# Power_supply.net
KiCad netlist of a schematic drawn in Altium Designer
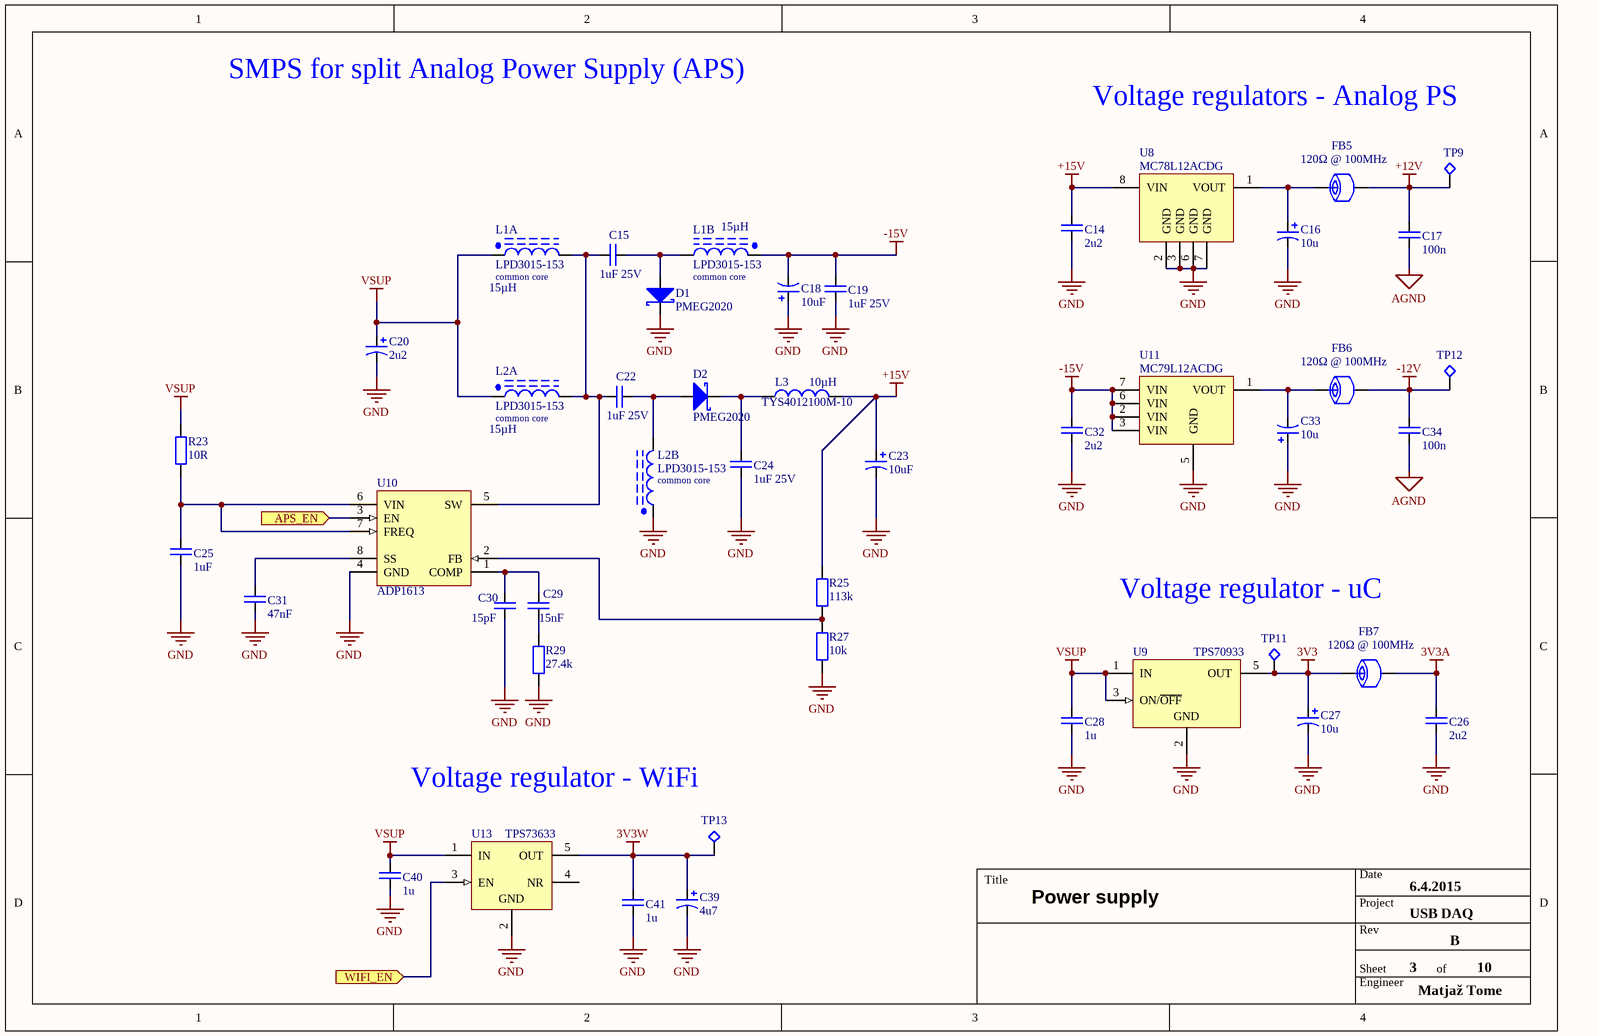
[diagram p0: Power_supply.SchDoc]

(export (version "E")
  (design (tool "Eeschema 10.0.6"))
  (components
    (comp (ref "C14")
      (value "2u2")
      (footprint "C_0603")
      (description "Generic capacitor")
      (libsource (lib "DAQ_REV_B") (part "Capacitor"))
    )
    (comp (ref "C15")
      (value "1uF 25V")
      (footprint "C_0603")
      (description "Generic capacitor")
      (libsource (lib "DAQ_REV_B") (part "Capacitor"))
    )
    (comp (ref "C16")
      (value "10u")
      (footprint "Tantalum Case A")
      (description "Generic polarized capacitor")
      (libsource (lib "DAQ_REV_B") (part "Capacitor - polarized"))
    )
    (comp (ref "C17")
      (value "100n")
      (footprint "C_0603")
      (description "Generic capacitor")
      (libsource (lib "DAQ_REV_B") (part "Capacitor"))
    )
    (comp (ref "C18")
      (value "10uF")
      (footprint "Tantalum Case A")
      (description "Generic polarized capacitor")
      (libsource (lib "DAQ_REV_B") (part "Capacitor - polarized"))
    )
    (comp (ref "C19")
      (value "1uF 25V")
      (footprint "C_0603")
      (description "Generic capacitor")
      (libsource (lib "DAQ_REV_B") (part "Capacitor"))
    )
    (comp (ref "C20")
      (value "2u2")
      (footprint "Tantalum Case A")
      (description "Generic polarized capacitor")
      (libsource (lib "DAQ_REV_B") (part "Capacitor - polarized"))
    )
    (comp (ref "C22")
      (value "1uF 25V")
      (footprint "C_0603")
      (description "Generic capacitor")
      (libsource (lib "DAQ_REV_B") (part "Capacitor"))
    )
    (comp (ref "C23")
      (value "10uF")
      (footprint "Tantalum Case A")
      (description "Generic polarized capacitor")
      (libsource (lib "DAQ_REV_B") (part "Capacitor - polarized"))
    )
    (comp (ref "C24")
      (value "1uF 25V")
      (footprint "C_0603")
      (description "Generic capacitor")
      (libsource (lib "DAQ_REV_B") (part "Capacitor"))
    )
    (comp (ref "C25")
      (value "1uF")
      (footprint "C_0603")
      (description "Generic capacitor")
      (libsource (lib "DAQ_REV_B") (part "Capacitor"))
    )
    (comp (ref "C26")
      (value "2u2")
      (footprint "C_0603")
      (description "Generic capacitor")
      (libsource (lib "DAQ_REV_B") (part "Capacitor"))
    )
    (comp (ref "C27")
      (value "10u")
      (footprint "Tantalum Case A")
      (description "Generic polarized capacitor")
      (libsource (lib "DAQ_REV_B") (part "Capacitor - polarized"))
    )
    (comp (ref "C28")
      (value "1u")
      (footprint "C_0603")
      (description "Generic capacitor")
      (libsource (lib "DAQ_REV_B") (part "Capacitor"))
    )
    (comp (ref "C29")
      (value "15nF")
      (footprint "C_0603")
      (description "Generic capacitor")
      (libsource (lib "DAQ_REV_B") (part "Capacitor"))
    )
    (comp (ref "C30")
      (value "15pF")
      (footprint "C_0603")
      (description "Generic capacitor")
      (libsource (lib "DAQ_REV_B") (part "Capacitor"))
    )
    (comp (ref "C31")
      (value "47nF")
      (footprint "C_0603")
      (description "Generic capacitor")
      (libsource (lib "DAQ_REV_B") (part "Capacitor"))
    )
    (comp (ref "C32")
      (value "2u2")
      (footprint "C_0603")
      (description "Generic capacitor")
      (libsource (lib "DAQ_REV_B") (part "Capacitor"))
    )
    (comp (ref "C33")
      (value "10u")
      (footprint "Tantalum Case A")
      (description "Generic polarized capacitor")
      (libsource (lib "DAQ_REV_B") (part "Capacitor - polarized"))
    )
    (comp (ref "C34")
      (value "100n")
      (footprint "C_0603")
      (description "Generic capacitor")
      (libsource (lib "DAQ_REV_B") (part "Capacitor"))
    )
    (comp (ref "C39")
      (value "4u7")
      (footprint "Tantalum Case A")
      (description "Generic polarized capacitor")
      (libsource (lib "DAQ_REV_B") (part "Capacitor - polarized"))
    )
    (comp (ref "C40")
      (value "1u")
      (footprint "C_0603")
      (description "Generic capacitor")
      (libsource (lib "DAQ_REV_B") (part "Capacitor"))
    )
    (comp (ref "C41")
      (value "1u")
      (footprint "C_0603")
      (description "Generic capacitor")
      (libsource (lib "DAQ_REV_B") (part "Capacitor"))
    )
    (comp (ref "D1")
      (value "PMEG2020")
      (footprint "SOD323")
      (description "Schottky Rectifier, 20 V, 2 A, Single, SOD-323, 2 Pins, 525 mV")
      (fields (field (name "MANUFACTURER") "Infineon"))
      (libsource (lib "DAQ_REV_B") (part "PMEG2020"))
    )
    (comp (ref "D2")
      (value "PMEG2020")
      (footprint "SOD323")
      (description "Schottky Rectifier, 20 V, 2 A, Single, SOD-323, 2 Pins, 525 mV")
      (fields (field (name "MANUFACTURER") "Infineon"))
      (libsource (lib "DAQ_REV_B") (part "PMEG2020"))
    )
    (comp (ref "FB5")
      (value "120Ω @ 100MHz")
      (footprint "SMD_0805")
      (description "Ferrite Bead, 0805 [2012 Metric], 120 ohm, 800 mA, BLM21A Series, 0.15 ohm, ± 25%")
      (fields (field (name "MANUFACTURER") "Murata"))
      (libsource (lib "DAQ_REV_B") (part "BLM21AG121SN1D"))
    )
    (comp (ref "FB6")
      (value "120Ω @ 100MHz")
      (footprint "SMD_0805")
      (description "Ferrite Bead, 0805 [2012 Metric], 120 ohm, 800 mA, BLM21A Series, 0.15 ohm, ± 25%")
      (fields (field (name "MANUFACTURER") "Murata"))
      (libsource (lib "DAQ_REV_B") (part "BLM21AG121SN1D"))
    )
    (comp (ref "FB7")
      (value "120Ω @ 100MHz")
      (footprint "SMD_0805")
      (description "Ferrite Bead, 0805 [2012 Metric], 120 ohm, 800 mA, BLM21A Series, 0.15 ohm, ± 25%")
      (fields (field (name "MANUFACTURER") "Murata"))
      (libsource (lib "DAQ_REV_B") (part "BLM21AG121SN1D"))
    )
    (comp (ref "L1")
      (value "LPD3015-153")
      (footprint "LPD3015")
      (description "Inductor, Coupled, 15 µH, 20%, 1.42 ohm, 460 mA, 3mm x 3mm x 1.4mm")
      (fields
        (field (name "MANUFACTURER") "Coilcraft")
        (field (name "ALTIUM_VALUE") "15µH")
        (field (name "TOLERANCE") "20%")
        (field (name "NOTE") "common core")
      )
      (libsource (lib "") (part "LPD3015-153_1"))
    )
    (comp (ref "L2")
      (value "LPD3015-153")
      (footprint "LPD3015")
      (description "Inductor, Coupled, 15 µH, 20%, 1.42 ohm, 460 mA, 3mm x 3mm x 1.4mm")
      (fields
        (field (name "MANUFACTURER") "Coilcraft")
        (field (name "ALTIUM_VALUE") "15µH")
        (field (name "TOLERANCE") "20%")
        (field (name "NOTE") "common core")
      )
      (libsource (lib "") (part "LPD3015-153_1"))
    )
    (comp (ref "L3")
      (value "10µH")
      (footprint "IND_SMD_4X4mm")
      (description "Power Inductor (SMD), 10 µH, 770 mA, Shielded, 800 mA, TYS Series, 4mm x 4mm x 1.2mm")
      (fields
        (field (name "MANUFACTURER") "Laird Technologies")
        (field (name "TOLERANCE") "20%")
        (field (name "MANUFACTURER NUMBER") "TYS4012100M-10")
      )
      (libsource (lib "DAQ_REV_B") (part "TYS4012100M-10"))
    )
    (comp (ref "R23")
      (value "10R")
      (footprint "R_0603")
      (description "Generic resistor")
      (libsource (lib "DAQ_REV_B") (part "Resistor"))
    )
    (comp (ref "R25")
      (value "113k")
      (footprint "R_0603")
      (description "Generic resistor")
      (libsource (lib "DAQ_REV_B") (part "Resistor"))
    )
    (comp (ref "R27")
      (value "10k")
      (footprint "R_0603")
      (description "Generic resistor")
      (libsource (lib "DAQ_REV_B") (part "Resistor"))
    )
    (comp (ref "R29")
      (value "27.4k")
      (footprint "R_0603")
      (description "Generic resistor")
      (libsource (lib "DAQ_REV_B") (part "Resistor"))
    )
    (comp (ref "TP9")
      (value "testpoint")
      (footprint "TP1_FULL")
      (description "testpoint 1.5mm diameter no hole")
      (fields (field (name "PART NUMBER") "XXC0006"))
      (libsource (lib "DAQ_REV_B") (part "Test Point"))
    )
    (comp (ref "TP11")
      (value "testpoint")
      (footprint "TP1_FULL")
      (description "testpoint 1.5mm diameter no hole")
      (fields (field (name "PART NUMBER") "XXC0006"))
      (libsource (lib "DAQ_REV_B") (part "Test Point"))
    )
    (comp (ref "TP12")
      (value "testpoint")
      (footprint "TP1_FULL")
      (description "testpoint 1.5mm diameter no hole")
      (fields (field (name "PART NUMBER") "XXC0006"))
      (libsource (lib "DAQ_REV_B") (part "Test Point"))
    )
    (comp (ref "TP13")
      (value "testpoint")
      (footprint "TP1_FULL")
      (description "testpoint 1.5mm diameter no hole")
      (fields (field (name "PART NUMBER") "XXC0006"))
      (libsource (lib "DAQ_REV_B") (part "Test Point"))
    )
    (comp (ref "U8")
      (value "MC78L12ACDG")
      (footprint "SOIC8")
      (description "100 mA Positive Voltage Regulator")
      (fields (field (name "PART NUMBER") "XLR0006") (field (name "MANUFACTURER") "ON Semiconductors"))
      (libsource (lib "DAQ_REV_B") (part "78LXX"))
    )
    (comp (ref "U9")
      (value "TPS70933")
      (footprint "SOT23-5")
      (description "1-µA IQ Voltage Regulators with Enable")
      (fields (field (name "PART NUMBER") "XLR0012") (field (name "MANUFACTURER") "Texas Instruments"))
      (libsource (lib "DAQ_REV_B") (part "TPS709XX"))
    )
    (comp (ref "U10")
      (value "ADP1613")
      (footprint "MSOP8")
      (description "DC-DC Switching Boost, SEPIC Regulator, Adjustable, 2.5V-5.5Vin, 3.6V-20Vout, 2Aout, MSOP-8")
      (fields (field (name "MANUFACTURER") "Analog devices"))
      (libsource (lib "DAQ") (part "ADP161X"))
    )
    (comp (ref "U11")
      (value "MC79L12ACDG")
      (footprint "SOIC8")
      (description "100 mA Negative Voltage Regulator")
      (fields (field (name "PART NUMBER") "XLR0007") (field (name "MANUFACTURER") "ON Semiconductors"))
      (libsource (lib "DAQ_REV_B") (part "79LXX"))
    )
    (comp (ref "U13")
      (value "TPS73633")
      (footprint "SOT23-5")
      (description "Cap-Free, NMOS, 400-mA Low-Dropout Regulator with Reverse Current Protection")
      (fields (field (name "PART NUMBER") "XLR0013") (field (name "MANUFACTURER") "Texas instruments"))
      (libsource (lib "DAQ_REV_B") (part "TPS736XX"))
    )
  )
  (nets
    (net (code "1") (name "+12V") (class "Default")
      (node (ref "C17") (pin "2") (pinfunction "2_2") (pintype "passive"))
      (node (ref "FB5") (pin "2") (pintype "passive"))
      (node (ref "TP9") (pin "1") (pinfunction "1_1") (pintype "passive"))
    )
    (net (code "2") (name "+15V") (class "Default")
      (node (ref "C14") (pin "1") (pinfunction "1_1") (pintype "passive"))
      (node (ref "C23") (pin "1") (pinfunction "1_1") (pintype "passive"))
      (node (ref "L3") (pin "2") (pinfunction "2_2") (pintype "passive"))
      (node (ref "R25") (pin "1") (pintype "passive"))
      (node (ref "U8") (pin "8") (pinfunction "VIN_8") (pintype "power_in"))
    )
    (net (code "3") (name "-12V") (class "Default")
      (node (ref "C34") (pin "2") (pinfunction "2_2") (pintype "passive"))
      (node (ref "FB6") (pin "2") (pintype "passive"))
      (node (ref "TP12") (pin "1") (pinfunction "1_1") (pintype "passive"))
    )
    (net (code "4") (name "-15V") (class "Default")
      (node (ref "C18") (pin "2") (pinfunction "2_2") (pintype "passive"))
      (node (ref "C19") (pin "2") (pinfunction "2_2") (pintype "passive"))
      (node (ref "C32") (pin "1") (pinfunction "1_1") (pintype "passive"))
      (node (ref "L1") (pin "4") (pinfunction "4_4") (pintype "passive"))
      (node (ref "U11") (pin "2") (pinfunction "VIN_2") (pintype "power_in"))
      (node (ref "U11") (pin "3") (pinfunction "VIN_3") (pintype "power_in"))
      (node (ref "U11") (pin "6") (pinfunction "VIN_6") (pintype "power_in"))
      (node (ref "U11") (pin "7") (pinfunction "VIN_7") (pintype "power_in"))
    )
    (net (code "5") (name "/APS_EN") (class "Default")
      (node (ref "U10") (pin "3") (pinfunction "EN_3") (pintype "input"))
    )
    (net (code "6") (name "/WIFI_EN") (class "Default")
      (node (ref "U13") (pin "3") (pinfunction "EN_3") (pintype "input"))
    )
    (net (code "7") (name "3V3") (class "Default")
      (node (ref "C27") (pin "1") (pinfunction "1_1") (pintype "passive"))
      (node (ref "FB7") (pin "1") (pintype "passive"))
      (node (ref "TP11") (pin "1") (pinfunction "1_1") (pintype "passive"))
      (node (ref "U9") (pin "5") (pinfunction "OUT_5") (pintype "power_in"))
    )
    (net (code "8") (name "3V3A") (class "Default")
      (node (ref "C26") (pin "1") (pinfunction "1_1") (pintype "passive"))
      (node (ref "FB7") (pin "2") (pintype "passive"))
    )
    (net (code "9") (name "3V3W") (class "Default")
      (node (ref "C39") (pin "1") (pinfunction "1_1") (pintype "passive"))
      (node (ref "C41") (pin "1") (pinfunction "1_1") (pintype "passive"))
      (node (ref "TP13") (pin "1") (pinfunction "1_1") (pintype "passive"))
      (node (ref "U13") (pin "5") (pinfunction "OUT_5") (pintype "power_in"))
    )
    (net (code "10") (name "AGND") (class "Default")
      (node (ref "C17") (pin "1") (pinfunction "1_1") (pintype "passive"))
      (node (ref "C34") (pin "1") (pinfunction "1_1") (pintype "passive"))
    )
    (net (code "11") (name "GND") (class "Default")
      (node (ref "C14") (pin "2") (pinfunction "2_2") (pintype "passive"))
      (node (ref "C16") (pin "2") (pinfunction "2_2") (pintype "passive"))
      (node (ref "C18") (pin "1") (pinfunction "1_1") (pintype "passive"))
      (node (ref "C19") (pin "1") (pinfunction "1_1") (pintype "passive"))
      (node (ref "C20") (pin "2") (pinfunction "2_2") (pintype "passive"))
      (node (ref "C23") (pin "2") (pinfunction "2_2") (pintype "passive"))
      (node (ref "C24") (pin "1") (pinfunction "1_1") (pintype "passive"))
      (node (ref "C25") (pin "2") (pinfunction "2_2") (pintype "passive"))
      (node (ref "C26") (pin "2") (pinfunction "2_2") (pintype "passive"))
      (node (ref "C27") (pin "2") (pinfunction "2_2") (pintype "passive"))
      (node (ref "C28") (pin "2") (pinfunction "2_2") (pintype "passive"))
      (node (ref "C30") (pin "2") (pinfunction "2_2") (pintype "passive"))
      (node (ref "C31") (pin "2") (pinfunction "2_2") (pintype "passive"))
      (node (ref "C32") (pin "2") (pinfunction "2_2") (pintype "passive"))
      (node (ref "C33") (pin "1") (pinfunction "1_1") (pintype "passive"))
      (node (ref "C39") (pin "2") (pinfunction "2_2") (pintype "passive"))
      (node (ref "C40") (pin "2") (pinfunction "2_2") (pintype "passive"))
      (node (ref "C41") (pin "2") (pinfunction "2_2") (pintype "passive"))
      (node (ref "D1") (pin "2") (pinfunction "K_2") (pintype "passive"))
      (node (ref "L2") (pin "4") (pinfunction "4_4") (pintype "passive"))
      (node (ref "R27") (pin "2") (pintype "passive"))
      (node (ref "R29") (pin "2") (pintype "passive"))
      (node (ref "U10") (pin "4") (pinfunction "GND_4") (pintype "power_in"))
      (node (ref "U11") (pin "5") (pinfunction "GND_5") (pintype "power_in"))
      (node (ref "U13") (pin "2") (pinfunction "GND_2") (pintype "power_in"))
      (node (ref "U8") (pin "2") (pinfunction "GND_2") (pintype "power_in"))
      (node (ref "U8") (pin "3") (pinfunction "GND_3") (pintype "power_in"))
      (node (ref "U8") (pin "6") (pinfunction "GND_6") (pintype "power_in"))
      (node (ref "U8") (pin "7") (pinfunction "GND_7") (pintype "power_in"))
      (node (ref "U9") (pin "2") (pinfunction "GND_2") (pintype "power_in"))
    )
    (net (code "12") (name "Net-(C29-Pad2)") (class "Default")
      (node (ref "C29") (pin "2") (pinfunction "2_2") (pintype "passive"))
      (node (ref "R29") (pin "1") (pintype "passive"))
    )
    (net (code "13") (name "Net-(D1-A)") (class "Default")
      (node (ref "C15") (pin "2") (pinfunction "2_2") (pintype "passive"))
      (node (ref "D1") (pin "1") (pinfunction "A_1") (pintype "passive"))
      (node (ref "L1") (pin "3") (pinfunction "3_3") (pintype "passive"))
    )
    (net (code "14") (name "Net-(D2-A)") (class "Default")
      (node (ref "C22") (pin "2") (pinfunction "2_2") (pintype "passive"))
      (node (ref "D2") (pin "1") (pinfunction "A_1") (pintype "passive"))
      (node (ref "L2") (pin "3") (pinfunction "3_3") (pintype "passive"))
    )
    (net (code "15") (name "Net-(D2-K)") (class "Default")
      (node (ref "C24") (pin "2") (pinfunction "2_2") (pintype "passive"))
      (node (ref "D2") (pin "2") (pinfunction "K_2") (pintype "passive"))
      (node (ref "L3") (pin "1") (pinfunction "1_1") (pintype "passive"))
    )
    (net (code "16") (name "Net-(U8-VOUT)") (class "Default")
      (node (ref "C16") (pin "1") (pinfunction "1_1") (pintype "passive"))
      (node (ref "FB5") (pin "1") (pintype "passive"))
      (node (ref "U8") (pin "1") (pinfunction "VOUT_1") (pintype "power_in"))
    )
    (net (code "17") (name "Net-(U10-COMP)") (class "Default")
      (node (ref "C29") (pin "1") (pinfunction "1_1") (pintype "passive"))
      (node (ref "C30") (pin "1") (pinfunction "1_1") (pintype "passive"))
      (node (ref "U10") (pin "1") (pinfunction "COMP_1") (pintype "passive"))
    )
    (net (code "18") (name "Net-(U10-FB)") (class "Default")
      (node (ref "R25") (pin "2") (pintype "passive"))
      (node (ref "R27") (pin "1") (pintype "passive"))
      (node (ref "U10") (pin "2") (pinfunction "FB_2") (pintype "input"))
    )
    (net (code "19") (name "Net-(U10-FREQ)") (class "Default")
      (node (ref "C25") (pin "1") (pinfunction "1_1") (pintype "passive"))
      (node (ref "R23") (pin "2") (pintype "passive"))
      (node (ref "U10") (pin "6") (pinfunction "VIN_6") (pintype "power_in"))
      (node (ref "U10") (pin "7") (pinfunction "FREQ_7") (pintype "input"))
    )
    (net (code "20") (name "Net-(U10-SS)") (class "Default")
      (node (ref "C31") (pin "1") (pinfunction "1_1") (pintype "passive"))
      (node (ref "U10") (pin "8") (pinfunction "SS_8") (pintype "passive"))
    )
    (net (code "21") (name "Net-(U10-SW)") (class "Default")
      (node (ref "C15") (pin "1") (pinfunction "1_1") (pintype "passive"))
      (node (ref "C22") (pin "1") (pinfunction "1_1") (pintype "passive"))
      (node (ref "L1") (pin "2") (pinfunction "2_2") (pintype "passive"))
      (node (ref "L2") (pin "2") (pinfunction "2_2") (pintype "passive"))
      (node (ref "U10") (pin "5") (pinfunction "SW_5") (pintype "passive"))
    )
    (net (code "22") (name "Net-(U11-VOUT)") (class "Default")
      (node (ref "C33") (pin "2") (pinfunction "2_2") (pintype "passive"))
      (node (ref "FB6") (pin "1") (pintype "passive"))
      (node (ref "U11") (pin "1") (pinfunction "VOUT_1") (pintype "power_in"))
    )
    (net (code "23") (name "VSUP") (class "Default")
      (node (ref "C20") (pin "1") (pinfunction "1_1") (pintype "passive"))
      (node (ref "C28") (pin "1") (pinfunction "1_1") (pintype "passive"))
      (node (ref "C40") (pin "1") (pinfunction "1_1") (pintype "passive"))
      (node (ref "L1") (pin "1") (pinfunction "1_1") (pintype "passive"))
      (node (ref "L2") (pin "1") (pinfunction "1_1") (pintype "passive"))
      (node (ref "R23") (pin "1") (pintype "passive"))
      (node (ref "U13") (pin "1") (pinfunction "IN_1") (pintype "power_in"))
      (node (ref "U9") (pin "1") (pinfunction "IN_1") (pintype "power_in"))
      (node (ref "U9") (pin "3") (pinfunction "ON/~{OFF}_3") (pintype "input"))
    )
    (net (code "24") (name "unconnected-(U13-NR-Pad4)") (class "Default")
      (node (ref "U13") (pin "4") (pinfunction "NR_4") (pintype "passive"))
    )
  )
)
